# 50_Distance.net
KiCad netlist of a schematic drawn in Altium Designer
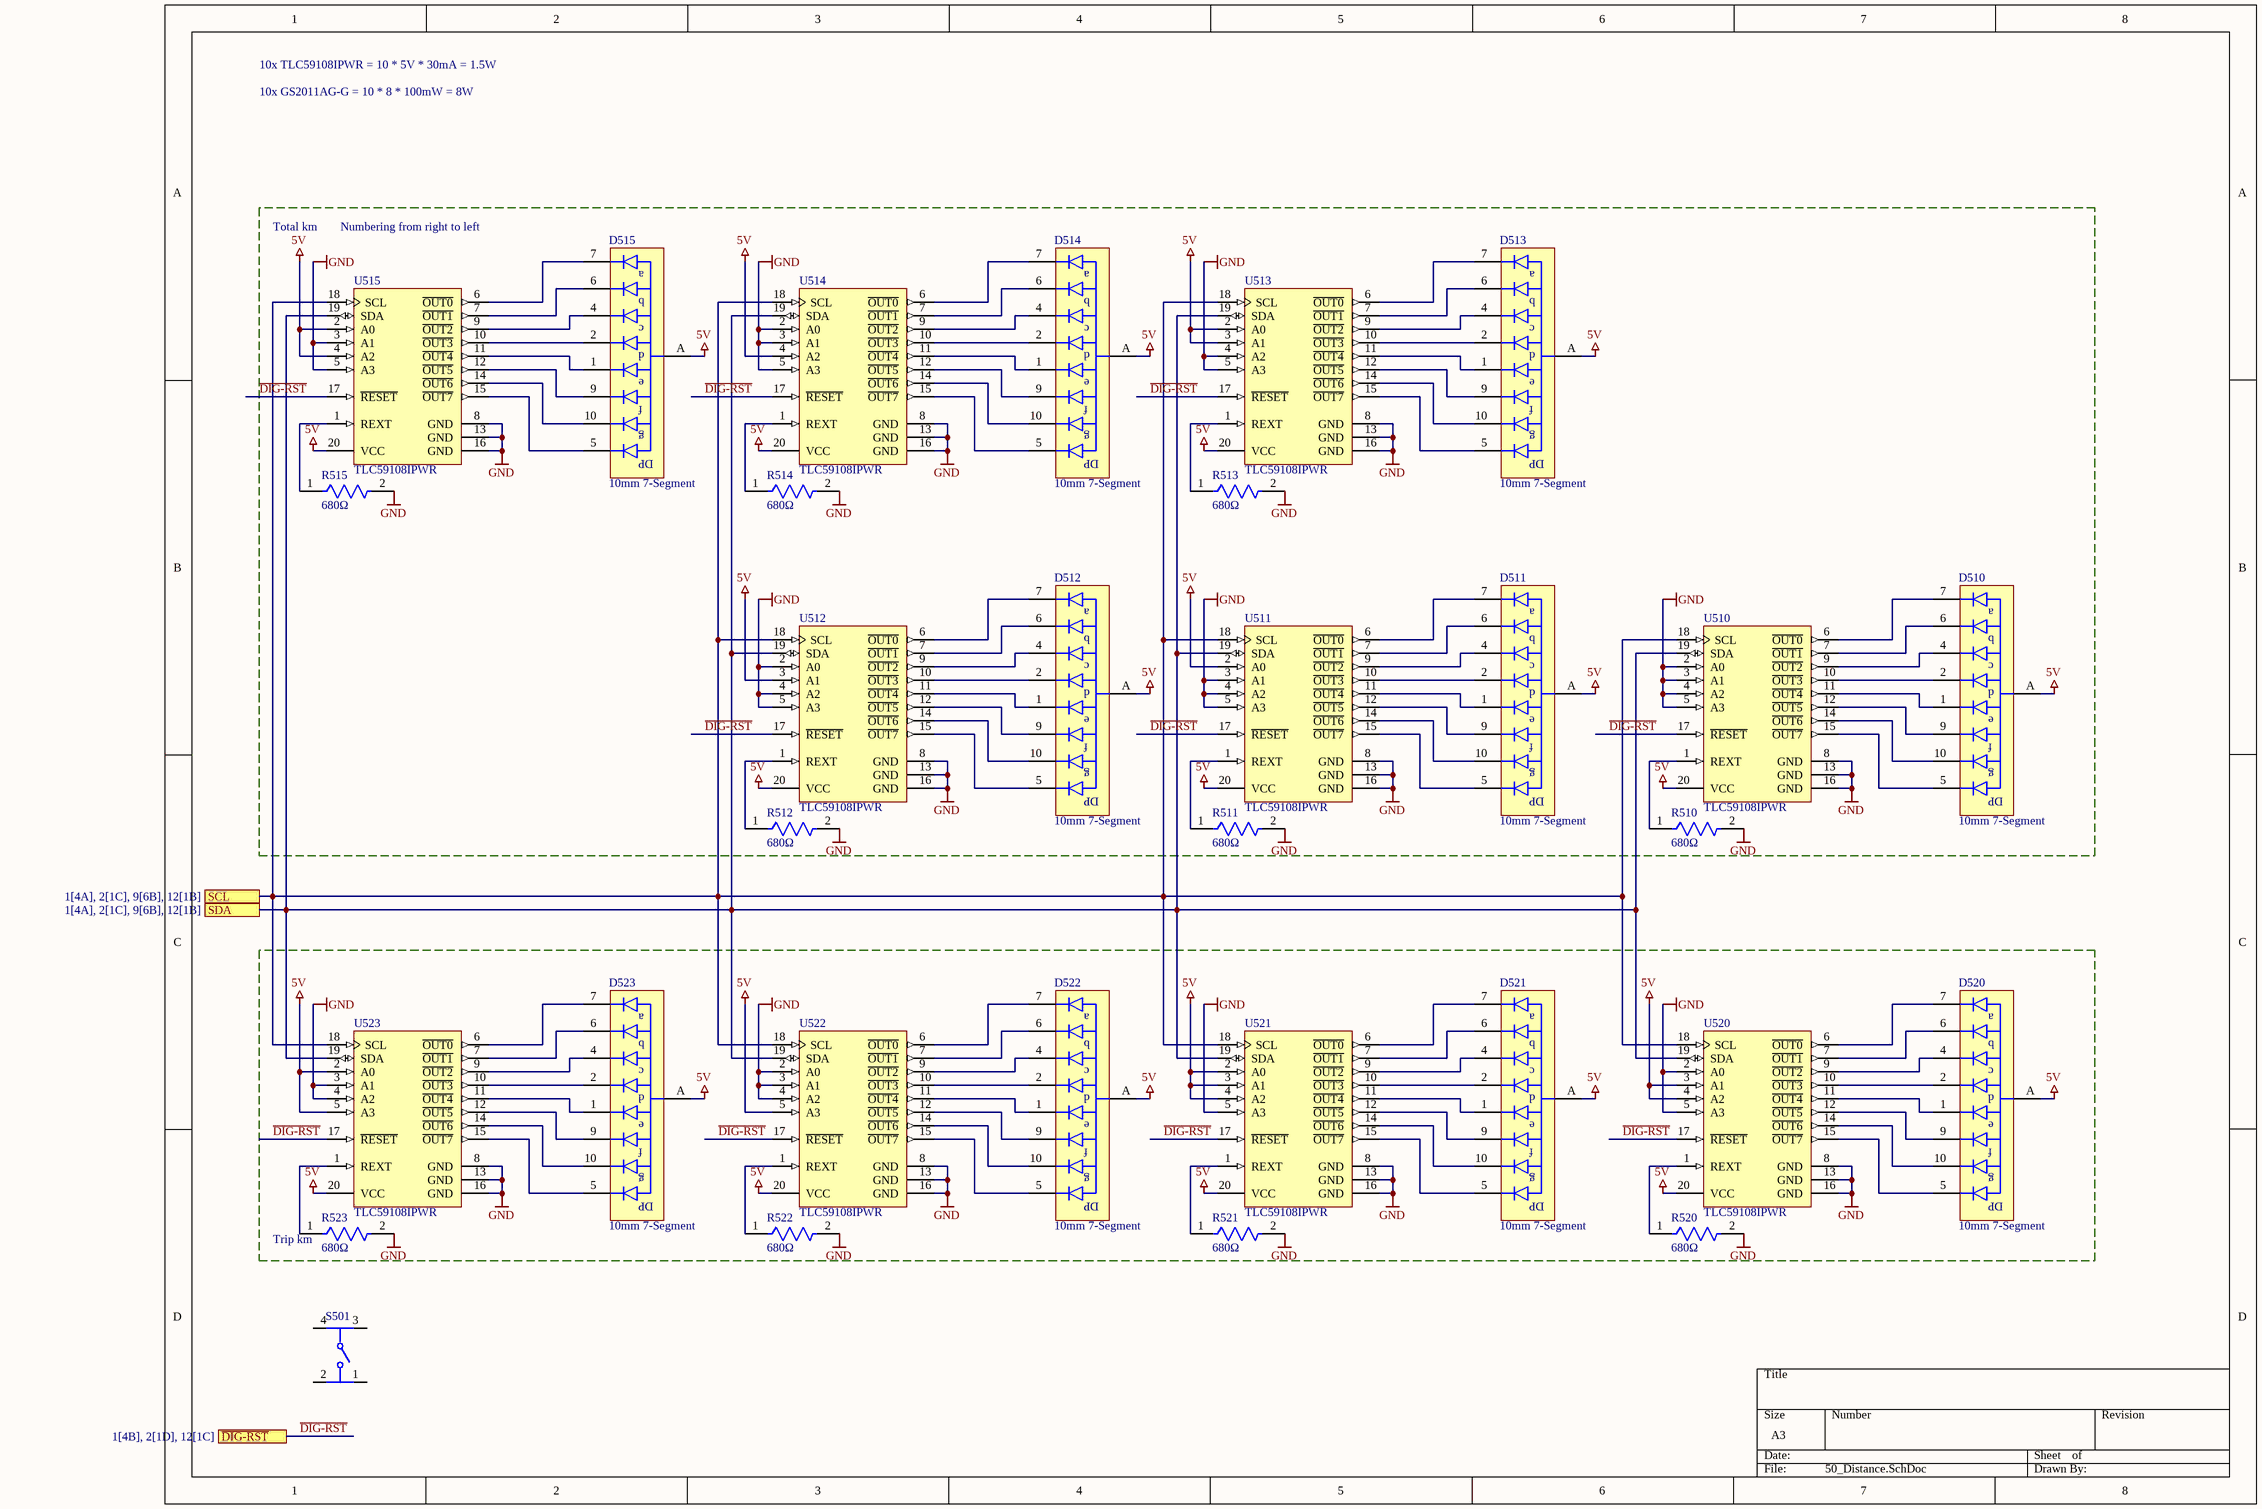
[diagram p0: 50_Distance.SchDoc]

(export (version "E")
  (design (tool "Eeschema 10.0.6"))
  (components
    (comp (ref "D510")
      (value "10mm 7-Segment")
      (footprint "GS2011AG-G")
      (description "SMD, 10x6.9mm 7-Segment")
      (libsource (lib "AltiumLib_MILUTIN") (part "GS2011AG-G"))
    )
    (comp (ref "D511")
      (value "10mm 7-Segment")
      (footprint "GS2011AG-G")
      (description "SMD, 10x6.9mm 7-Segment")
      (libsource (lib "AltiumLib_MILUTIN") (part "GS2011AG-G"))
    )
    (comp (ref "D512")
      (value "10mm 7-Segment")
      (footprint "GS2011AG-G")
      (description "SMD, 10x6.9mm 7-Segment")
      (libsource (lib "AltiumLib_MILUTIN") (part "GS2011AG-G"))
    )
    (comp (ref "D513")
      (value "10mm 7-Segment")
      (footprint "GS2011AG-G")
      (description "SMD, 10x6.9mm 7-Segment")
      (libsource (lib "AltiumLib_MILUTIN") (part "GS2011AG-G"))
    )
    (comp (ref "D514")
      (value "10mm 7-Segment")
      (footprint "GS2011AG-G")
      (description "SMD, 10x6.9mm 7-Segment")
      (libsource (lib "AltiumLib_MILUTIN") (part "GS2011AG-G"))
    )
    (comp (ref "D515")
      (value "10mm 7-Segment")
      (footprint "GS2011AG-G")
      (description "SMD, 10x6.9mm 7-Segment")
      (libsource (lib "AltiumLib_MILUTIN") (part "GS2011AG-G"))
    )
    (comp (ref "D520")
      (value "10mm 7-Segment")
      (footprint "GS2011AG-G")
      (description "SMD, 10x6.9mm 7-Segment")
      (libsource (lib "AltiumLib_MILUTIN") (part "GS2011AG-G"))
    )
    (comp (ref "D521")
      (value "10mm 7-Segment")
      (footprint "GS2011AG-G")
      (description "SMD, 10x6.9mm 7-Segment")
      (libsource (lib "AltiumLib_MILUTIN") (part "GS2011AG-G"))
    )
    (comp (ref "D522")
      (value "10mm 7-Segment")
      (footprint "GS2011AG-G")
      (description "SMD, 10x6.9mm 7-Segment")
      (libsource (lib "AltiumLib_MILUTIN") (part "GS2011AG-G"))
    )
    (comp (ref "D523")
      (value "10mm 7-Segment")
      (footprint "GS2011AG-G")
      (description "SMD, 10x6.9mm 7-Segment")
      (libsource (lib "AltiumLib_MILUTIN") (part "GS2011AG-G"))
    )
    (comp (ref "R510")
      (value "680Ω")
      (footprint "FP-CRCW0603-e3-IPC_A")
      (description "RES Thick Film, 680Ω, 5%, 0.1W, 200ppm/°C, 0603\r\nCRCW0603680RJNEA")
      (fields (field (name "TOLERANCE") "5%"))
      (libsource (lib "Altium Content Vault") (part "1029c3af85768c4190bb7ad29bc67b5"))
    )
    (comp (ref "R511")
      (value "680Ω")
      (footprint "FP-CRCW0603-e3-IPC_A")
      (description "RES Thick Film, 680Ω, 5%, 0.1W, 200ppm/°C, 0603\r\nCRCW0603680RJNEA")
      (fields (field (name "TOLERANCE") "5%"))
      (libsource (lib "Altium Content Vault") (part "1029c3af85768c4190bb7ad29bc67b5"))
    )
    (comp (ref "R512")
      (value "680Ω")
      (footprint "FP-CRCW0603-e3-IPC_A")
      (description "RES Thick Film, 680Ω, 5%, 0.1W, 200ppm/°C, 0603\r\nCRCW0603680RJNEA")
      (fields (field (name "TOLERANCE") "5%"))
      (libsource (lib "Altium Content Vault") (part "1029c3af85768c4190bb7ad29bc67b5"))
    )
    (comp (ref "R513")
      (value "680Ω")
      (footprint "FP-CRCW0603-e3-IPC_A")
      (description "RES Thick Film, 680Ω, 5%, 0.1W, 200ppm/°C, 0603\r\nCRCW0603680RJNEA")
      (fields (field (name "TOLERANCE") "5%"))
      (libsource (lib "Altium Content Vault") (part "1029c3af85768c4190bb7ad29bc67b5"))
    )
    (comp (ref "R514")
      (value "680Ω")
      (footprint "FP-CRCW0603-e3-IPC_A")
      (description "RES Thick Film, 680Ω, 5%, 0.1W, 200ppm/°C, 0603\r\nCRCW0603680RJNEA")
      (fields (field (name "TOLERANCE") "5%"))
      (libsource (lib "Altium Content Vault") (part "1029c3af85768c4190bb7ad29bc67b5"))
    )
    (comp (ref "R515")
      (value "680Ω")
      (footprint "FP-CRCW0603-e3-IPC_A")
      (description "RES Thick Film, 680Ω, 5%, 0.1W, 200ppm/°C, 0603\r\nCRCW0603680RJNEA")
      (fields (field (name "TOLERANCE") "5%"))
      (libsource (lib "Altium Content Vault") (part "1029c3af85768c4190bb7ad29bc67b5"))
    )
    (comp (ref "R520")
      (value "680Ω")
      (footprint "FP-CRCW0603-e3-IPC_A")
      (description "RES Thick Film, 680Ω, 5%, 0.1W, 200ppm/°C, 0603\r\nCRCW0603680RJNEA")
      (fields (field (name "TOLERANCE") "5%"))
      (libsource (lib "Altium Content Vault") (part "1029c3af85768c4190bb7ad29bc67b5"))
    )
    (comp (ref "R521")
      (value "680Ω")
      (footprint "FP-CRCW0603-e3-IPC_A")
      (description "RES Thick Film, 680Ω, 5%, 0.1W, 200ppm/°C, 0603\r\nCRCW0603680RJNEA")
      (fields (field (name "TOLERANCE") "5%"))
      (libsource (lib "Altium Content Vault") (part "1029c3af85768c4190bb7ad29bc67b5"))
    )
    (comp (ref "R522")
      (value "680Ω")
      (footprint "FP-CRCW0603-e3-IPC_A")
      (description "RES Thick Film, 680Ω, 5%, 0.1W, 200ppm/°C, 0603\r\nCRCW0603680RJNEA")
      (fields (field (name "TOLERANCE") "5%"))
      (libsource (lib "Altium Content Vault") (part "1029c3af85768c4190bb7ad29bc67b5"))
    )
    (comp (ref "R523")
      (value "680Ω")
      (footprint "FP-CRCW0603-e3-IPC_A")
      (description "RES Thick Film, 680Ω, 5%, 0.1W, 200ppm/°C, 0603\r\nCRCW0603680RJNEA")
      (fields (field (name "TOLERANCE") "5%"))
      (libsource (lib "Altium Content Vault") (part "1029c3af85768c4190bb7ad29bc67b5"))
    )
    (comp (ref "S501")
      (value "~")
      (footprint "FP-PTS645SM43SMTR92LFS-MFG")
      (description "SWITCH TACTILE SPST-NO 0.05A 12V\r\nPTS645SM43SMTR92LFS")
      (libsource (lib "Altium Content Vault") (part "1adf0dd01260c80cf25a44bfd6b99ba"))
    )
    (comp (ref "U510")
      (value "TLC59108IPWR")
      (footprint "PW0020A_M")
      (fields (field (name "MANUFACTURER") "Texas Instruments"))
      (libsource (lib "Altium Content Vault") (part "TI-TLC59108PW20"))
    )
    (comp (ref "U511")
      (value "TLC59108IPWR")
      (footprint "PW0020A_M")
      (fields (field (name "MANUFACTURER") "Texas Instruments"))
      (libsource (lib "Altium Content Vault") (part "TI-TLC59108PW20"))
    )
    (comp (ref "U512")
      (value "TLC59108IPWR")
      (footprint "PW0020A_M")
      (fields (field (name "MANUFACTURER") "Texas Instruments"))
      (libsource (lib "Altium Content Vault") (part "TI-TLC59108PW20"))
    )
    (comp (ref "U513")
      (value "TLC59108IPWR")
      (footprint "PW0020A_M")
      (fields (field (name "MANUFACTURER") "Texas Instruments"))
      (libsource (lib "Altium Content Vault") (part "TI-TLC59108PW20"))
    )
    (comp (ref "U514")
      (value "TLC59108IPWR")
      (footprint "PW0020A_M")
      (fields (field (name "MANUFACTURER") "Texas Instruments"))
      (libsource (lib "Altium Content Vault") (part "TI-TLC59108PW20"))
    )
    (comp (ref "U515")
      (value "TLC59108IPWR")
      (footprint "PW0020A_M")
      (fields (field (name "MANUFACTURER") "Texas Instruments"))
      (libsource (lib "Altium Content Vault") (part "TI-TLC59108PW20"))
    )
    (comp (ref "U520")
      (value "TLC59108IPWR")
      (footprint "PW0020A_M")
      (fields (field (name "MANUFACTURER") "Texas Instruments"))
      (libsource (lib "Altium Content Vault") (part "TI-TLC59108PW20"))
    )
    (comp (ref "U521")
      (value "TLC59108IPWR")
      (footprint "PW0020A_M")
      (fields (field (name "MANUFACTURER") "Texas Instruments"))
      (libsource (lib "Altium Content Vault") (part "TI-TLC59108PW20"))
    )
    (comp (ref "U522")
      (value "TLC59108IPWR")
      (footprint "PW0020A_M")
      (fields (field (name "MANUFACTURER") "Texas Instruments"))
      (libsource (lib "Altium Content Vault") (part "TI-TLC59108PW20"))
    )
    (comp (ref "U523")
      (value "TLC59108IPWR")
      (footprint "PW0020A_M")
      (fields (field (name "MANUFACTURER") "Texas Instruments"))
      (libsource (lib "Altium Content Vault") (part "TI-TLC59108PW20"))
    )
  )
  (nets
    (net (code "1") (name "/SCL") (class "Default")
      (node (ref "U510") (pin "18") (pinfunction "SCL_18") (pintype "input"))
      (node (ref "U511") (pin "18") (pinfunction "SCL_18") (pintype "input"))
      (node (ref "U512") (pin "18") (pinfunction "SCL_18") (pintype "input"))
      (node (ref "U513") (pin "18") (pinfunction "SCL_18") (pintype "input"))
      (node (ref "U514") (pin "18") (pinfunction "SCL_18") (pintype "input"))
      (node (ref "U515") (pin "18") (pinfunction "SCL_18") (pintype "input"))
      (node (ref "U520") (pin "18") (pinfunction "SCL_18") (pintype "input"))
      (node (ref "U521") (pin "18") (pinfunction "SCL_18") (pintype "input"))
      (node (ref "U522") (pin "18") (pinfunction "SCL_18") (pintype "input"))
      (node (ref "U523") (pin "18") (pinfunction "SCL_18") (pintype "input"))
    )
    (net (code "2") (name "/SDA") (class "Default")
      (node (ref "U510") (pin "19") (pinfunction "SDA_19") (pintype "bidirectional"))
      (node (ref "U511") (pin "19") (pinfunction "SDA_19") (pintype "bidirectional"))
      (node (ref "U512") (pin "19") (pinfunction "SDA_19") (pintype "bidirectional"))
      (node (ref "U513") (pin "19") (pinfunction "SDA_19") (pintype "bidirectional"))
      (node (ref "U514") (pin "19") (pinfunction "SDA_19") (pintype "bidirectional"))
      (node (ref "U515") (pin "19") (pinfunction "SDA_19") (pintype "bidirectional"))
      (node (ref "U520") (pin "19") (pinfunction "SDA_19") (pintype "bidirectional"))
      (node (ref "U521") (pin "19") (pinfunction "SDA_19") (pintype "bidirectional"))
      (node (ref "U522") (pin "19") (pinfunction "SDA_19") (pintype "bidirectional"))
      (node (ref "U523") (pin "19") (pinfunction "SDA_19") (pintype "bidirectional"))
    )
    (net (code "3") (name "/~{DIG-RST}") (class "Default")
      (node (ref "U510") (pin "17") (pinfunction "~{RESET}_17") (pintype "input"))
      (node (ref "U511") (pin "17") (pinfunction "~{RESET}_17") (pintype "input"))
      (node (ref "U512") (pin "17") (pinfunction "~{RESET}_17") (pintype "input"))
      (node (ref "U513") (pin "17") (pinfunction "~{RESET}_17") (pintype "input"))
      (node (ref "U514") (pin "17") (pinfunction "~{RESET}_17") (pintype "input"))
      (node (ref "U515") (pin "17") (pinfunction "~{RESET}_17") (pintype "input"))
      (node (ref "U520") (pin "17") (pinfunction "~{RESET}_17") (pintype "input"))
      (node (ref "U521") (pin "17") (pinfunction "~{RESET}_17") (pintype "input"))
      (node (ref "U522") (pin "17") (pinfunction "~{RESET}_17") (pintype "input"))
      (node (ref "U523") (pin "17") (pinfunction "~{RESET}_17") (pintype "input"))
    )
    (net (code "4") (name "5V") (class "Default")
      (node (ref "D510") (pin "A") (pinfunction "A_A") (pintype "passive"))
      (node (ref "D511") (pin "A") (pinfunction "A_A") (pintype "passive"))
      (node (ref "D512") (pin "A") (pinfunction "A_A") (pintype "passive"))
      (node (ref "D513") (pin "A") (pinfunction "A_A") (pintype "passive"))
      (node (ref "D514") (pin "A") (pinfunction "A_A") (pintype "passive"))
      (node (ref "D515") (pin "A") (pinfunction "A_A") (pintype "passive"))
      (node (ref "D520") (pin "A") (pinfunction "A_A") (pintype "passive"))
      (node (ref "D521") (pin "A") (pinfunction "A_A") (pintype "passive"))
      (node (ref "D522") (pin "A") (pinfunction "A_A") (pintype "passive"))
      (node (ref "D523") (pin "A") (pinfunction "A_A") (pintype "passive"))
      (node (ref "U510") (pin "20") (pinfunction "VCC_20") (pintype "power_in"))
      (node (ref "U511") (pin "2") (pinfunction "A0_2") (pintype "input"))
      (node (ref "U511") (pin "20") (pinfunction "VCC_20") (pintype "power_in"))
      (node (ref "U512") (pin "20") (pinfunction "VCC_20") (pintype "power_in"))
      (node (ref "U512") (pin "3") (pinfunction "A1_3") (pintype "input"))
      (node (ref "U513") (pin "2") (pinfunction "A0_2") (pintype "input"))
      (node (ref "U513") (pin "20") (pinfunction "VCC_20") (pintype "power_in"))
      (node (ref "U513") (pin "3") (pinfunction "A1_3") (pintype "input"))
      (node (ref "U514") (pin "20") (pinfunction "VCC_20") (pintype "power_in"))
      (node (ref "U514") (pin "4") (pinfunction "A2_4") (pintype "input"))
      (node (ref "U515") (pin "2") (pinfunction "A0_2") (pintype "input"))
      (node (ref "U515") (pin "20") (pinfunction "VCC_20") (pintype "power_in"))
      (node (ref "U515") (pin "4") (pinfunction "A2_4") (pintype "input"))
      (node (ref "U520") (pin "20") (pinfunction "VCC_20") (pintype "power_in"))
      (node (ref "U520") (pin "3") (pinfunction "A1_3") (pintype "input"))
      (node (ref "U520") (pin "4") (pinfunction "A2_4") (pintype "input"))
      (node (ref "U521") (pin "2") (pinfunction "A0_2") (pintype "input"))
      (node (ref "U521") (pin "20") (pinfunction "VCC_20") (pintype "power_in"))
      (node (ref "U521") (pin "3") (pinfunction "A1_3") (pintype "input"))
      (node (ref "U521") (pin "4") (pinfunction "A2_4") (pintype "input"))
      (node (ref "U522") (pin "20") (pinfunction "VCC_20") (pintype "power_in"))
      (node (ref "U522") (pin "5") (pinfunction "A3_5") (pintype "input"))
      (node (ref "U523") (pin "2") (pinfunction "A0_2") (pintype "input"))
      (node (ref "U523") (pin "20") (pinfunction "VCC_20") (pintype "power_in"))
      (node (ref "U523") (pin "5") (pinfunction "A3_5") (pintype "input"))
    )
    (net (code "5") (name "GND") (class "Default")
      (node (ref "R510") (pin "2") (pinfunction "2_2") (pintype "passive"))
      (node (ref "R511") (pin "2") (pinfunction "2_2") (pintype "passive"))
      (node (ref "R512") (pin "2") (pinfunction "2_2") (pintype "passive"))
      (node (ref "R513") (pin "2") (pinfunction "2_2") (pintype "passive"))
      (node (ref "R514") (pin "2") (pinfunction "2_2") (pintype "passive"))
      (node (ref "R515") (pin "2") (pinfunction "2_2") (pintype "passive"))
      (node (ref "R520") (pin "2") (pinfunction "2_2") (pintype "passive"))
      (node (ref "R521") (pin "2") (pinfunction "2_2") (pintype "passive"))
      (node (ref "R522") (pin "2") (pinfunction "2_2") (pintype "passive"))
      (node (ref "R523") (pin "2") (pinfunction "2_2") (pintype "passive"))
      (node (ref "U510") (pin "13") (pinfunction "GND_13") (pintype "power_in"))
      (node (ref "U510") (pin "16") (pinfunction "GND_16") (pintype "power_in"))
      (node (ref "U510") (pin "2") (pinfunction "A0_2") (pintype "input"))
      (node (ref "U510") (pin "3") (pinfunction "A1_3") (pintype "input"))
      (node (ref "U510") (pin "4") (pinfunction "A2_4") (pintype "input"))
      (node (ref "U510") (pin "5") (pinfunction "A3_5") (pintype "input"))
      (node (ref "U510") (pin "8") (pinfunction "GND_8") (pintype "power_in"))
      (node (ref "U511") (pin "13") (pinfunction "GND_13") (pintype "power_in"))
      (node (ref "U511") (pin "16") (pinfunction "GND_16") (pintype "power_in"))
      (node (ref "U511") (pin "3") (pinfunction "A1_3") (pintype "input"))
      (node (ref "U511") (pin "4") (pinfunction "A2_4") (pintype "input"))
      (node (ref "U511") (pin "5") (pinfunction "A3_5") (pintype "input"))
      (node (ref "U511") (pin "8") (pinfunction "GND_8") (pintype "power_in"))
      (node (ref "U512") (pin "13") (pinfunction "GND_13") (pintype "power_in"))
      (node (ref "U512") (pin "16") (pinfunction "GND_16") (pintype "power_in"))
      (node (ref "U512") (pin "2") (pinfunction "A0_2") (pintype "input"))
      (node (ref "U512") (pin "4") (pinfunction "A2_4") (pintype "input"))
      (node (ref "U512") (pin "5") (pinfunction "A3_5") (pintype "input"))
      (node (ref "U512") (pin "8") (pinfunction "GND_8") (pintype "power_in"))
      (node (ref "U513") (pin "13") (pinfunction "GND_13") (pintype "power_in"))
      (node (ref "U513") (pin "16") (pinfunction "GND_16") (pintype "power_in"))
      (node (ref "U513") (pin "4") (pinfunction "A2_4") (pintype "input"))
      (node (ref "U513") (pin "5") (pinfunction "A3_5") (pintype "input"))
      (node (ref "U513") (pin "8") (pinfunction "GND_8") (pintype "power_in"))
      (node (ref "U514") (pin "13") (pinfunction "GND_13") (pintype "power_in"))
      (node (ref "U514") (pin "16") (pinfunction "GND_16") (pintype "power_in"))
      (node (ref "U514") (pin "2") (pinfunction "A0_2") (pintype "input"))
      (node (ref "U514") (pin "3") (pinfunction "A1_3") (pintype "input"))
      (node (ref "U514") (pin "5") (pinfunction "A3_5") (pintype "input"))
      (node (ref "U514") (pin "8") (pinfunction "GND_8") (pintype "power_in"))
      (node (ref "U515") (pin "13") (pinfunction "GND_13") (pintype "power_in"))
      (node (ref "U515") (pin "16") (pinfunction "GND_16") (pintype "power_in"))
      (node (ref "U515") (pin "3") (pinfunction "A1_3") (pintype "input"))
      (node (ref "U515") (pin "5") (pinfunction "A3_5") (pintype "input"))
      (node (ref "U515") (pin "8") (pinfunction "GND_8") (pintype "power_in"))
      (node (ref "U520") (pin "13") (pinfunction "GND_13") (pintype "power_in"))
      (node (ref "U520") (pin "16") (pinfunction "GND_16") (pintype "power_in"))
      (node (ref "U520") (pin "2") (pinfunction "A0_2") (pintype "input"))
      (node (ref "U520") (pin "5") (pinfunction "A3_5") (pintype "input"))
      (node (ref "U520") (pin "8") (pinfunction "GND_8") (pintype "power_in"))
      (node (ref "U521") (pin "13") (pinfunction "GND_13") (pintype "power_in"))
      (node (ref "U521") (pin "16") (pinfunction "GND_16") (pintype "power_in"))
      (node (ref "U521") (pin "5") (pinfunction "A3_5") (pintype "input"))
      (node (ref "U521") (pin "8") (pinfunction "GND_8") (pintype "power_in"))
      (node (ref "U522") (pin "13") (pinfunction "GND_13") (pintype "power_in"))
      (node (ref "U522") (pin "16") (pinfunction "GND_16") (pintype "power_in"))
      (node (ref "U522") (pin "2") (pinfunction "A0_2") (pintype "input"))
      (node (ref "U522") (pin "3") (pinfunction "A1_3") (pintype "input"))
      (node (ref "U522") (pin "4") (pinfunction "A2_4") (pintype "input"))
      (node (ref "U522") (pin "8") (pinfunction "GND_8") (pintype "power_in"))
      (node (ref "U523") (pin "13") (pinfunction "GND_13") (pintype "power_in"))
      (node (ref "U523") (pin "16") (pinfunction "GND_16") (pintype "power_in"))
      (node (ref "U523") (pin "3") (pinfunction "A1_3") (pintype "input"))
      (node (ref "U523") (pin "4") (pinfunction "A2_4") (pintype "input"))
      (node (ref "U523") (pin "8") (pinfunction "GND_8") (pintype "power_in"))
    )
    (net (code "6") (name "Net-(U510-REXT)") (class "Default")
      (node (ref "R510") (pin "1") (pinfunction "1_1") (pintype "passive"))
      (node (ref "U510") (pin "1") (pinfunction "REXT_1") (pintype "input"))
    )
    (net (code "7") (name "Net-(U510-~{OUT0})") (class "Default")
      (node (ref "D510") (pin "7") (pinfunction "7_7") (pintype "passive"))
      (node (ref "U510") (pin "6") (pinfunction "~{OUT0}_6") (pintype "output"))
    )
    (net (code "8") (name "Net-(U510-~{OUT1})") (class "Default")
      (node (ref "D510") (pin "6") (pinfunction "6_6") (pintype "passive"))
      (node (ref "U510") (pin "7") (pinfunction "~{OUT1}_7") (pintype "output"))
    )
    (net (code "9") (name "Net-(U510-~{OUT2})") (class "Default")
      (node (ref "D510") (pin "4") (pinfunction "4_4") (pintype "passive"))
      (node (ref "U510") (pin "9") (pinfunction "~{OUT2}_9") (pintype "output"))
    )
    (net (code "10") (name "Net-(U510-~{OUT3})") (class "Default")
      (node (ref "D510") (pin "2") (pinfunction "2_2") (pintype "passive"))
      (node (ref "U510") (pin "10") (pinfunction "~{OUT3}_10") (pintype "output"))
    )
    (net (code "11") (name "Net-(U510-~{OUT4})") (class "Default")
      (node (ref "D510") (pin "1") (pinfunction "1_1") (pintype "passive"))
      (node (ref "U510") (pin "11") (pinfunction "~{OUT4}_11") (pintype "output"))
    )
    (net (code "12") (name "Net-(U510-~{OUT5})") (class "Default")
      (node (ref "D510") (pin "9") (pinfunction "9_9") (pintype "passive"))
      (node (ref "U510") (pin "12") (pinfunction "~{OUT5}_12") (pintype "output"))
    )
    (net (code "13") (name "Net-(U510-~{OUT6})") (class "Default")
      (node (ref "D510") (pin "10") (pinfunction "10_10") (pintype "passive"))
      (node (ref "U510") (pin "14") (pinfunction "~{OUT6}_14") (pintype "output"))
    )
    (net (code "14") (name "Net-(U510-~{OUT7})") (class "Default")
      (node (ref "D510") (pin "5") (pinfunction "5_5") (pintype "passive"))
      (node (ref "U510") (pin "15") (pinfunction "~{OUT7}_15") (pintype "output"))
    )
    (net (code "15") (name "Net-(U511-REXT)") (class "Default")
      (node (ref "R511") (pin "1") (pinfunction "1_1") (pintype "passive"))
      (node (ref "U511") (pin "1") (pinfunction "REXT_1") (pintype "input"))
    )
    (net (code "16") (name "Net-(U511-~{OUT0})") (class "Default")
      (node (ref "D511") (pin "7") (pinfunction "7_7") (pintype "passive"))
      (node (ref "U511") (pin "6") (pinfunction "~{OUT0}_6") (pintype "output"))
    )
    (net (code "17") (name "Net-(U511-~{OUT1})") (class "Default")
      (node (ref "D511") (pin "6") (pinfunction "6_6") (pintype "passive"))
      (node (ref "U511") (pin "7") (pinfunction "~{OUT1}_7") (pintype "output"))
    )
    (net (code "18") (name "Net-(U511-~{OUT2})") (class "Default")
      (node (ref "D511") (pin "4") (pinfunction "4_4") (pintype "passive"))
      (node (ref "U511") (pin "9") (pinfunction "~{OUT2}_9") (pintype "output"))
    )
    (net (code "19") (name "Net-(U511-~{OUT3})") (class "Default")
      (node (ref "D511") (pin "2") (pinfunction "2_2") (pintype "passive"))
      (node (ref "U511") (pin "10") (pinfunction "~{OUT3}_10") (pintype "output"))
    )
    (net (code "20") (name "Net-(U511-~{OUT4})") (class "Default")
      (node (ref "D511") (pin "1") (pinfunction "1_1") (pintype "passive"))
      (node (ref "U511") (pin "11") (pinfunction "~{OUT4}_11") (pintype "output"))
    )
    (net (code "21") (name "Net-(U511-~{OUT5})") (class "Default")
      (node (ref "D511") (pin "9") (pinfunction "9_9") (pintype "passive"))
      (node (ref "U511") (pin "12") (pinfunction "~{OUT5}_12") (pintype "output"))
    )
    (net (code "22") (name "Net-(U511-~{OUT6})") (class "Default")
      (node (ref "D511") (pin "10") (pinfunction "10_10") (pintype "passive"))
      (node (ref "U511") (pin "14") (pinfunction "~{OUT6}_14") (pintype "output"))
    )
    (net (code "23") (name "Net-(U511-~{OUT7})") (class "Default")
      (node (ref "D511") (pin "5") (pinfunction "5_5") (pintype "passive"))
      (node (ref "U511") (pin "15") (pinfunction "~{OUT7}_15") (pintype "output"))
    )
    (net (code "24") (name "Net-(U512-REXT)") (class "Default")
      (node (ref "R512") (pin "1") (pinfunction "1_1") (pintype "passive"))
      (node (ref "U512") (pin "1") (pinfunction "REXT_1") (pintype "input"))
    )
    (net (code "25") (name "Net-(U512-~{OUT0})") (class "Default")
      (node (ref "D512") (pin "7") (pinfunction "7_7") (pintype "passive"))
      (node (ref "U512") (pin "6") (pinfunction "~{OUT0}_6") (pintype "output"))
    )
    (net (code "26") (name "Net-(U512-~{OUT1})") (class "Default")
      (node (ref "D512") (pin "6") (pinfunction "6_6") (pintype "passive"))
      (node (ref "U512") (pin "7") (pinfunction "~{OUT1}_7") (pintype "output"))
    )
    (net (code "27") (name "Net-(U512-~{OUT2})") (class "Default")
      (node (ref "D512") (pin "4") (pinfunction "4_4") (pintype "passive"))
      (node (ref "U512") (pin "9") (pinfunction "~{OUT2}_9") (pintype "output"))
    )
    (net (code "28") (name "Net-(U512-~{OUT3})") (class "Default")
      (node (ref "D512") (pin "2") (pinfunction "2_2") (pintype "passive"))
      (node (ref "U512") (pin "10") (pinfunction "~{OUT3}_10") (pintype "output"))
    )
    (net (code "29") (name "Net-(U512-~{OUT4})") (class "Default")
      (node (ref "D512") (pin "1") (pinfunction "1_1") (pintype "passive"))
      (node (ref "U512") (pin "11") (pinfunction "~{OUT4}_11") (pintype "output"))
    )
    (net (code "30") (name "Net-(U512-~{OUT5})") (class "Default")
      (node (ref "D512") (pin "9") (pinfunction "9_9") (pintype "passive"))
      (node (ref "U512") (pin "12") (pinfunction "~{OUT5}_12") (pintype "output"))
    )
    (net (code "31") (name "Net-(U512-~{OUT6})") (class "Default")
      (node (ref "D512") (pin "10") (pinfunction "10_10") (pintype "passive"))
      (node (ref "U512") (pin "14") (pinfunction "~{OUT6}_14") (pintype "output"))
    )
    (net (code "32") (name "Net-(U512-~{OUT7})") (class "Default")
      (node (ref "D512") (pin "5") (pinfunction "5_5") (pintype "passive"))
      (node (ref "U512") (pin "15") (pinfunction "~{OUT7}_15") (pintype "output"))
    )
    (net (code "33") (name "Net-(U513-REXT)") (class "Default")
      (node (ref "R513") (pin "1") (pinfunction "1_1") (pintype "passive"))
      (node (ref "U513") (pin "1") (pinfunction "REXT_1") (pintype "input"))
    )
    (net (code "34") (name "Net-(U513-~{OUT0})") (class "Default")
      (node (ref "D513") (pin "7") (pinfunction "7_7") (pintype "passive"))
      (node (ref "U513") (pin "6") (pinfunction "~{OUT0}_6") (pintype "output"))
    )
    (net (code "35") (name "Net-(U513-~{OUT1})") (class "Default")
      (node (ref "D513") (pin "6") (pinfunction "6_6") (pintype "passive"))
      (node (ref "U513") (pin "7") (pinfunction "~{OUT1}_7") (pintype "output"))
    )
    (net (code "36") (name "Net-(U513-~{OUT2})") (class "Default")
      (node (ref "D513") (pin "4") (pinfunction "4_4") (pintype "passive"))
      (node (ref "U513") (pin "9") (pinfunction "~{OUT2}_9") (pintype "output"))
    )
    (net (code "37") (name "Net-(U513-~{OUT3})") (class "Default")
      (node (ref "D513") (pin "2") (pinfunction "2_2") (pintype "passive"))
      (node (ref "U513") (pin "10") (pinfunction "~{OUT3}_10") (pintype "output"))
    )
    (net (code "38") (name "Net-(U513-~{OUT4})") (class "Default")
      (node (ref "D513") (pin "1") (pinfunction "1_1") (pintype "passive"))
      (node (ref "U513") (pin "11") (pinfunction "~{OUT4}_11") (pintype "output"))
    )
    (net (code "39") (name "Net-(U513-~{OUT5})") (class "Default")
      (node (ref "D513") (pin "9") (pinfunction "9_9") (pintype "passive"))
      (node (ref "U513") (pin "12") (pinfunction "~{OUT5}_12") (pintype "output"))
    )
    (net (code "40") (name "Net-(U513-~{OUT6})") (class "Default")
      (node (ref "D513") (pin "10") (pinfunction "10_10") (pintype "passive"))
      (node (ref "U513") (pin "14") (pinfunction "~{OUT6}_14") (pintype "output"))
    )
    (net (code "41") (name "Net-(U513-~{OUT7})") (class "Default")
      (node (ref "D513") (pin "5") (pinfunction "5_5") (pintype "passive"))
      (node (ref "U513") (pin "15") (pinfunction "~{OUT7}_15") (pintype "output"))
    )
    (net (code "42") (name "Net-(U514-REXT)") (class "Default")
      (node (ref "R514") (pin "1") (pinfunction "1_1") (pintype "passive"))
      (node (ref "U514") (pin "1") (pinfunction "REXT_1") (pintype "input"))
    )
    (net (code "43") (name "Net-(U514-~{OUT0})") (class "Default")
      (node (ref "D514") (pin "7") (pinfunction "7_7") (pintype "passive"))
      (node (ref "U514") (pin "6") (pinfunction "~{OUT0}_6") (pintype "output"))
    )
    (net (code "44") (name "Net-(U514-~{OUT1})") (class "Default")
      (node (ref "D514") (pin "6") (pinfunction "6_6") (pintype "passive"))
      (node (ref "U514") (pin "7") (pinfunction "~{OUT1}_7") (pintype "output"))
    )
    (net (code "45") (name "Net-(U514-~{OUT2})") (class "Default")
      (node (ref "D514") (pin "4") (pinfunction "4_4") (pintype "passive"))
      (node (ref "U514") (pin "9") (pinfunction "~{OUT2}_9") (pintype "output"))
    )
    (net (code "46") (name "Net-(U514-~{OUT3})") (class "Default")
      (node (ref "D514") (pin "2") (pinfunction "2_2") (pintype "passive"))
      (node (ref "U514") (pin "10") (pinfunction "~{OUT3}_10") (pintype "output"))
    )
    (net (code "47") (name "Net-(U514-~{OUT4})") (class "Default")
      (node (ref "D514") (pin "1") (pinfunction "1_1") (pintype "passive"))
      (node (ref "U514") (pin "11") (pinfunction "~{OUT4}_11") (pintype "output"))
    )
    (net (code "48") (name "Net-(U514-~{OUT5})") (class "Default")
      (node (ref "D514") (pin "9") (pinfunction "9_9") (pintype "passive"))
      (node (ref "U514") (pin "12") (pinfunction "~{OUT5}_12") (pintype "output"))
    )
    (net (code "49") (name "Net-(U514-~{OUT6})") (class "Default")
      (node (ref "D514") (pin "10") (pinfunction "10_10") (pintype "passive"))
      (node (ref "U514") (pin "14") (pinfunction "~{OUT6}_14") (pintype "output"))
    )
    (net (code "50") (name "Net-(U514-~{OUT7})") (class "Default")
      (node (ref "D514") (pin "5") (pinfunction "5_5") (pintype "passive"))
      (node (ref "U514") (pin "15") (pinfunction "~{OUT7}_15") (pintype "output"))
    )
    (net (code "51") (name "Net-(U515-REXT)") (class "Default")
      (node (ref "R515") (pin "1") (pinfunction "1_1") (pintype "passive"))
      (node (ref "U515") (pin "1") (pinfunction "REXT_1") (pintype "input"))
    )
    (net (code "52") (name "Net-(U515-~{OUT0})") (class "Default")
      (node (ref "D515") (pin "7") (pinfunction "7_7") (pintype "passive"))
      (node (ref "U515") (pin "6") (pinfunction "~{OUT0}_6") (pintype "output"))
    )
    (net (code "53") (name "Net-(U515-~{OUT1})") (class "Default")
      (node (ref "D515") (pin "6") (pinfunction "6_6") (pintype "passive"))
      (node (ref "U515") (pin "7") (pinfunction "~{OUT1}_7") (pintype "output"))
    )
    (net (code "54") (name "Net-(U515-~{OUT2})") (class "Default")
      (node (ref "D515") (pin "4") (pinfunction "4_4") (pintype "passive"))
      (node (ref "U515") (pin "9") (pinfunction "~{OUT2}_9") (pintype "output"))
    )
    (net (code "55") (name "Net-(U515-~{OUT3})") (class "Default")
      (node (ref "D515") (pin "2") (pinfunction "2_2") (pintype "passive"))
      (node (ref "U515") (pin "10") (pinfunction "~{OUT3}_10") (pintype "output"))
    )
    (net (code "56") (name "Net-(U515-~{OUT4})") (class "Default")
      (node (ref "D515") (pin "1") (pinfunction "1_1") (pintype "passive"))
      (node (ref "U515") (pin "11") (pinfunction "~{OUT4}_11") (pintype "output"))
    )
    (net (code "57") (name "Net-(U515-~{OUT5})") (class "Default")
      (node (ref "D515") (pin "9") (pinfunction "9_9") (pintype "passive"))
      (node (ref "U515") (pin "12") (pinfunction "~{OUT5}_12") (pintype "output"))
    )
    (net (code "58") (name "Net-(U515-~{OUT6})") (class "Default")
      (node (ref "D515") (pin "10") (pinfunction "10_10") (pintype "passive"))
      (node (ref "U515") (pin "14") (pinfunction "~{OUT6}_14") (pintype "output"))
    )
    (net (code "59") (name "Net-(U515-~{OUT7})") (class "Default")
      (node (ref "D515") (pin "5") (pinfunction "5_5") (pintype "passive"))
      (node (ref "U515") (pin "15") (pinfunction "~{OUT7}_15") (pintype "output"))
    )
    (net (code "60") (name "Net-(U520-REXT)") (class "Default")
      (node (ref "R520") (pin "1") (pinfunction "1_1") (pintype "passive"))
      (node (ref "U520") (pin "1") (pinfunction "REXT_1") (pintype "input"))
    )
    (net (code "61") (name "Net-(U520-~{OUT0})") (class "Default")
      (node (ref "D520") (pin "7") (pinfunction "7_7") (pintype "passive"))
      (node (ref "U520") (pin "6") (pinfunction "~{OUT0}_6") (pintype "output"))
    )
    (net (code "62") (name "Net-(U520-~{OUT1})") (class "Default")
      (node (ref "D520") (pin "6") (pinfunction "6_6") (pintype "passive"))
      (node (ref "U520") (pin "7") (pinfunction "~{OUT1}_7") (pintype "output"))
    )
    (net (code "63") (name "Net-(U520-~{OUT2})") (class "Default")
      (node (ref "D520") (pin "4") (pinfunction "4_4") (pintype "passive"))
      (node (ref "U520") (pin "9") (pinfunction "~{OUT2}_9") (pintype "output"))
    )
    (net (code "64") (name "Net-(U520-~{OUT3})") (class "Default")
      (node (ref "D520") (pin "2") (pinfunction "2_2") (pintype "passive"))
      (node (ref "U520") (pin "10") (pinfunction "~{OUT3}_10") (pintype "output"))
    )
    (net (code "65") (name "Net-(U520-~{OUT4})") (class "Default")
      (node (ref "D520") (pin "1") (pinfunction "1_1") (pintype "passive"))
      (node (ref "U520") (pin "11") (pinfunction "~{OUT4}_11") (pintype "output"))
    )
    (net (code "66") (name "Net-(U520-~{OUT5})") (class "Default")
      (node (ref "D520") (pin "9") (pinfunction "9_9") (pintype "passive"))
      (node (ref "U520") (pin "12") (pinfunction "~{OUT5}_12") (pintype "output"))
    )
    (net (code "67") (name "Net-(U520-~{OUT6})") (class "Default")
      (node (ref "D520") (pin "10") (pinfunction "10_10") (pintype "passive"))
      (node (ref "U520") (pin "14") (pinfunction "~{OUT6}_14") (pintype "output"))
    )
    (net (code "68") (name "Net-(U520-~{OUT7})") (class "Default")
      (node (ref "D520") (pin "5") (pinfunction "5_5") (pintype "passive"))
      (node (ref "U520") (pin "15") (pinfunction "~{OUT7}_15") (pintype "output"))
    )
    (net (code "69") (name "Net-(U521-REXT)") (class "Default")
      (node (ref "R521") (pin "1") (pinfunction "1_1") (pintype "passive"))
      (node (ref "U521") (pin "1") (pinfunction "REXT_1") (pintype "input"))
    )
    (net (code "70") (name "Net-(U521-~{OUT0})") (class "Default")
      (node (ref "D521") (pin "7") (pinfunction "7_7") (pintype "passive"))
      (node (ref "U521") (pin "6") (pinfunction "~{OUT0}_6") (pintype "output"))
    )
    (net (code "71") (name "Net-(U521-~{OUT1})") (class "Default")
      (node (ref "D521") (pin "6") (pinfunction "6_6") (pintype "passive"))
      (node (ref "U521") (pin "7") (pinfunction "~{OUT1}_7") (pintype "output"))
    )
    (net (code "72") (name "Net-(U521-~{OUT2})") (class "Default")
      (node (ref "D521") (pin "4") (pinfunction "4_4") (pintype "passive"))
      (node (ref "U521") (pin "9") (pinfunction "~{OUT2}_9") (pintype "output"))
    )
    (net (code "73") (name "Net-(U521-~{OUT3})") (class "Default")
      (node (ref "D521") (pin "2") (pinfunction "2_2") (pintype "passive"))
      (node (ref "U521") (pin "10") (pinfunction "~{OUT3}_10") (pintype "output"))
    )
    (net (code "74") (name "Net-(U521-~{OUT4})") (class "Default")
      (node (ref "D521") (pin "1") (pinfunction "1_1") (pintype "passive"))
      (node (ref "U521") (pin "11") (pinfunction "~{OUT4}_11") (pintype "output"))
    )
    (net (code "75") (name "Net-(U521-~{OUT5})") (class "Default")
      (node (ref "D521") (pin "9") (pinfunction "9_9") (pintype "passive"))
      (node (ref "U521") (pin "12") (pinfunction "~{OUT5}_12") (pintype "output"))
    )
    (net (code "76") (name "Net-(U521-~{OUT6})") (class "Default")
      (node (ref "D521") (pin "10") (pinfunction "10_10") (pintype "passive"))
      (node (ref "U521") (pin "14") (pinfunction "~{OUT6}_14") (pintype "output"))
    )
    (net (code "77") (name "Net-(U521-~{OUT7})") (class "Default")
      (node (ref "D521") (pin "5") (pinfunction "5_5") (pintype "passive"))
      (node (ref "U521") (pin "15") (pinfunction "~{OUT7}_15") (pintype "output"))
    )
    (net (code "78") (name "Net-(U522-REXT)") (class "Default")
      (node (ref "R522") (pin "1") (pinfunction "1_1") (pintype "passive"))
      (node (ref "U522") (pin "1") (pinfunction "REXT_1") (pintype "input"))
    )
    (net (code "79") (name "Net-(U522-~{OUT0})") (class "Default")
      (node (ref "D522") (pin "7") (pinfunction "7_7") (pintype "passive"))
      (node (ref "U522") (pin "6") (pinfunction "~{OUT0}_6") (pintype "output"))
    )
    (net (code "80") (name "Net-(U522-~{OUT1})") (class "Default")
      (node (ref "D522") (pin "6") (pinfunction "6_6") (pintype "passive"))
      (node (ref "U522") (pin "7") (pinfunction "~{OUT1}_7") (pintype "output"))
    )
    (net (code "81") (name "Net-(U522-~{OUT2})") (class "Default")
      (node (ref "D522") (pin "4") (pinfunction "4_4") (pintype "passive"))
      (node (ref "U522") (pin "9") (pinfunction "~{OUT2}_9") (pintype "output"))
    )
    (net (code "82") (name "Net-(U522-~{OUT3})") (class "Default")
      (node (ref "D522") (pin "2") (pinfunction "2_2") (pintype "passive"))
      (node (ref "U522") (pin "10") (pinfunction "~{OUT3}_10") (pintype "output"))
    )
    (net (code "83") (name "Net-(U522-~{OUT4})") (class "Default")
      (node (ref "D522") (pin "1") (pinfunction "1_1") (pintype "passive"))
      (node (ref "U522") (pin "11") (pinfunction "~{OUT4}_11") (pintype "output"))
    )
    (net (code "84") (name "Net-(U522-~{OUT5})") (class "Default")
      (node (ref "D522") (pin "9") (pinfunction "9_9") (pintype "passive"))
      (node (ref "U522") (pin "12") (pinfunction "~{OUT5}_12") (pintype "output"))
    )
    (net (code "85") (name "Net-(U522-~{OUT6})") (class "Default")
      (node (ref "D522") (pin "10") (pinfunction "10_10") (pintype "passive"))
      (node (ref "U522") (pin "14") (pinfunction "~{OUT6}_14") (pintype "output"))
    )
    (net (code "86") (name "Net-(U522-~{OUT7})") (class "Default")
      (node (ref "D522") (pin "5") (pinfunction "5_5") (pintype "passive"))
      (node (ref "U522") (pin "15") (pinfunction "~{OUT7}_15") (pintype "output"))
    )
    (net (code "87") (name "Net-(U523-REXT)") (class "Default")
      (node (ref "R523") (pin "1") (pinfunction "1_1") (pintype "passive"))
      (node (ref "U523") (pin "1") (pinfunction "REXT_1") (pintype "input"))
    )
    (net (code "88") (name "Net-(U523-~{OUT0})") (class "Default")
      (node (ref "D523") (pin "7") (pinfunction "7_7") (pintype "passive"))
      (node (ref "U523") (pin "6") (pinfunction "~{OUT0}_6") (pintype "output"))
    )
    (net (code "89") (name "Net-(U523-~{OUT1})") (class "Default")
      (node (ref "D523") (pin "6") (pinfunction "6_6") (pintype "passive"))
      (node (ref "U523") (pin "7") (pinfunction "~{OUT1}_7") (pintype "output"))
    )
    (net (code "90") (name "Net-(U523-~{OUT2})") (class "Default")
      (node (ref "D523") (pin "4") (pinfunction "4_4") (pintype "passive"))
      (node (ref "U523") (pin "9") (pinfunction "~{OUT2}_9") (pintype "output"))
    )
    (net (code "91") (name "Net-(U523-~{OUT3})") (class "Default")
      (node (ref "D523") (pin "2") (pinfunction "2_2") (pintype "passive"))
      (node (ref "U523") (pin "10") (pinfunction "~{OUT3}_10") (pintype "output"))
    )
    (net (code "92") (name "Net-(U523-~{OUT4})") (class "Default")
      (node (ref "D523") (pin "1") (pinfunction "1_1") (pintype "passive"))
      (node (ref "U523") (pin "11") (pinfunction "~{OUT4}_11") (pintype "output"))
    )
    (net (code "93") (name "Net-(U523-~{OUT5})") (class "Default")
      (node (ref "D523") (pin "9") (pinfunction "9_9") (pintype "passive"))
      (node (ref "U523") (pin "12") (pinfunction "~{OUT5}_12") (pintype "output"))
    )
    (net (code "94") (name "Net-(U523-~{OUT6})") (class "Default")
      (node (ref "D523") (pin "10") (pinfunction "10_10") (pintype "passive"))
      (node (ref "U523") (pin "14") (pinfunction "~{OUT6}_14") (pintype "output"))
    )
    (net (code "95") (name "Net-(U523-~{OUT7})") (class "Default")
      (node (ref "D523") (pin "5") (pinfunction "5_5") (pintype "passive"))
      (node (ref "U523") (pin "15") (pinfunction "~{OUT7}_15") (pintype "output"))
    )
    (net (code "96") (name "unconnected-(S501-Pad1)") (class "Default")
      (node (ref "S501") (pin "1") (pinfunction "1_1") (pintype "passive"))
    )
    (net (code "97") (name "unconnected-(S501-Pad2)") (class "Default")
      (node (ref "S501") (pin "2") (pinfunction "2_2") (pintype "passive"))
    )
    (net (code "98") (name "unconnected-(S501-Pad3)") (class "Default")
      (node (ref "S501") (pin "3") (pinfunction "3_3") (pintype "passive"))
    )
    (net (code "99") (name "unconnected-(S501-Pad4)") (class "Default")
      (node (ref "S501") (pin "4") (pinfunction "4_4") (pintype "passive"))
    )
  )
)
